# LMZ10500.net
KiCad netlist of a schematic drawn in Altium Designer
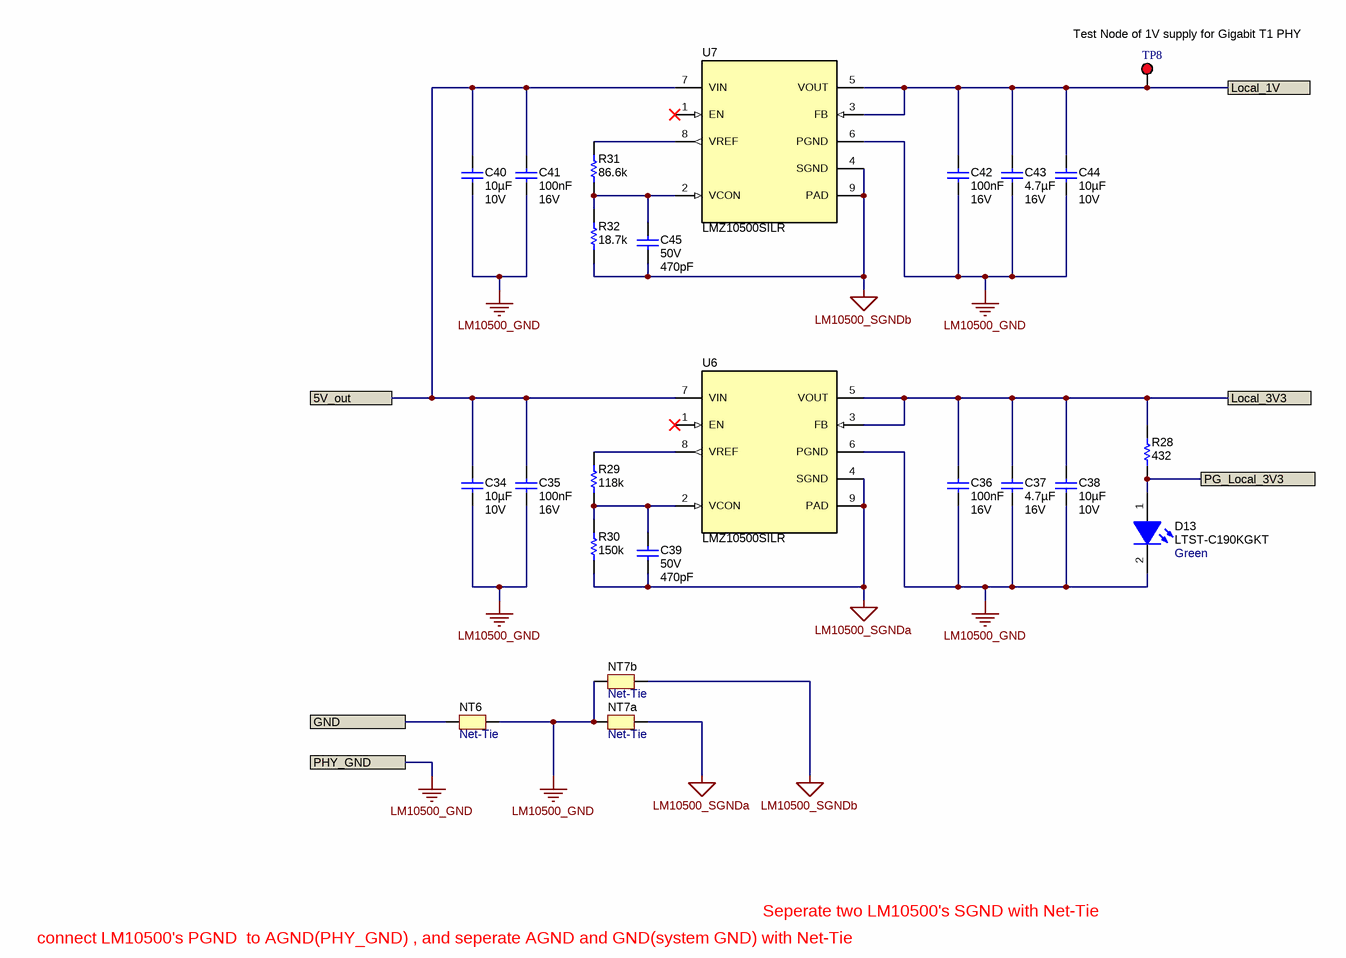
[diagram p0: LMZ10500.SchDoc]

(export (version "E")
  (design (tool "Eeschema 10.0.6"))
  (components
    (comp (ref "C34")
      (value "GRM188Z71A106MA73D")
      (footprint "0603")
      (description "CAP, CERM, 10 uF, 10 V, +/- 20%, X7R, 0603")
      (fields
        (field (name "MANUFACTURER") "MuRata")
        (field (name "CAP_F") "10µF")
        (field (name "VDC_V") "10V")
        (field (name "PUBLISHER") "Texas Instruments")
      )
      (libsource (lib "Altium Vault - TI") (part "Capacitor"))
    )
    (comp (ref "C35")
      (value "GRM188R71C104KA01D")
      (footprint "0603")
      (description "CAP, CERM, 0.1 uF, 16 V, +/- 10%, X7R, 0603")
      (fields
        (field (name "MANUFACTURER") "MuRata")
        (field (name "CAP_F") "100nF")
        (field (name "VDC_V") "16V")
        (field (name "PUBLISHER") "Texas Instruments")
      )
      (libsource (lib "Altium Vault - TI") (part "Capacitor"))
    )
    (comp (ref "C36")
      (value "GRM188R71C104KA01D")
      (footprint "0603")
      (description "CAP, CERM, 0.1 uF, 16 V, +/- 10%, X7R, 0603")
      (fields
        (field (name "MANUFACTURER") "MuRata")
        (field (name "CAP_F") "100nF")
        (field (name "VDC_V") "16V")
        (field (name "PUBLISHER") "Texas Instruments")
      )
      (libsource (lib "Altium Vault - TI") (part "Capacitor"))
    )
    (comp (ref "C37")
      (value "GRM188Z71C475KE21D")
      (footprint "0603")
      (description "CAP, CERM, 4.7 uF, 16 V,+/- 10%, X7R, 0603")
      (fields
        (field (name "MANUFACTURER") "MuRata")
        (field (name "CAP_F") "4.7µF")
        (field (name "VDC_V") "16V")
        (field (name "PUBLISHER") "Texas Instruments")
      )
      (libsource (lib "Altium Vault - TI") (part "Capacitor"))
    )
    (comp (ref "C38")
      (value "GRM188Z71A106MA73D")
      (footprint "0603")
      (description "CAP, CERM, 10 uF, 10 V, +/- 20%, X7R, 0603")
      (fields
        (field (name "MANUFACTURER") "MuRata")
        (field (name "CAP_F") "10µF")
        (field (name "VDC_V") "10V")
        (field (name "PUBLISHER") "Texas Instruments")
      )
      (libsource (lib "Altium Vault - TI") (part "Capacitor"))
    )
    (comp (ref "C39")
      (value "GCM155R71H471KA37D")
      (footprint "0402")
      (description "CAP, CERM, 470 pF, 50 V, +/- 10%, X7R, AEC-Q200 Grade 1, 0402")
      (fields
        (field (name "MANUFACTURER") "MuRata")
        (field (name "VDC_V") "50V")
        (field (name "VALUEDISPLAYED") "470pF")
        (field (name "PUBLISHER") "Texas Instruments")
      )
      (libsource (lib "Altium Vault - TI") (part "Capacitor"))
    )
    (comp (ref "C40")
      (value "GRM188Z71A106MA73D")
      (footprint "0603")
      (description "CAP, CERM, 10 uF, 10 V, +/- 20%, X7R, 0603")
      (fields
        (field (name "MANUFACTURER") "MuRata")
        (field (name "CAP_F") "10µF")
        (field (name "VDC_V") "10V")
        (field (name "PUBLISHER") "Texas Instruments")
      )
      (libsource (lib "Altium Vault - TI") (part "Capacitor"))
    )
    (comp (ref "C41")
      (value "GRM188R71C104KA01D")
      (footprint "0603")
      (description "CAP, CERM, 0.1 uF, 16 V, +/- 10%, X7R, 0603")
      (fields
        (field (name "MANUFACTURER") "MuRata")
        (field (name "CAP_F") "100nF")
        (field (name "VDC_V") "16V")
        (field (name "PUBLISHER") "Texas Instruments")
      )
      (libsource (lib "Altium Vault - TI") (part "Capacitor"))
    )
    (comp (ref "C42")
      (value "GRM188R71C104KA01D")
      (footprint "0603")
      (description "CAP, CERM, 0.1 uF, 16 V, +/- 10%, X7R, 0603")
      (fields
        (field (name "MANUFACTURER") "MuRata")
        (field (name "CAP_F") "100nF")
        (field (name "VDC_V") "16V")
        (field (name "PUBLISHER") "Texas Instruments")
      )
      (libsource (lib "Altium Vault - TI") (part "Capacitor"))
    )
    (comp (ref "C43")
      (value "GRM188Z71C475KE21D")
      (footprint "0603")
      (description "CAP, CERM, 4.7 uF, 16 V,+/- 10%, X7R, 0603")
      (fields
        (field (name "MANUFACTURER") "MuRata")
        (field (name "CAP_F") "4.7µF")
        (field (name "VDC_V") "16V")
        (field (name "PUBLISHER") "Texas Instruments")
      )
      (libsource (lib "Altium Vault - TI") (part "Capacitor"))
    )
    (comp (ref "C44")
      (value "GRM188Z71A106MA73D")
      (footprint "0603")
      (description "CAP, CERM, 10 uF, 10 V, +/- 20%, X7R, 0603")
      (fields
        (field (name "MANUFACTURER") "MuRata")
        (field (name "CAP_F") "10µF")
        (field (name "VDC_V") "10V")
        (field (name "PUBLISHER") "Texas Instruments")
      )
      (libsource (lib "Altium Vault - TI") (part "Capacitor"))
    )
    (comp (ref "C45")
      (value "GCM155R71H471KA37D")
      (footprint "0402")
      (description "CAP, CERM, 470 pF, 50 V, +/- 10%, X7R, AEC-Q200 Grade 1, 0402")
      (fields
        (field (name "MANUFACTURER") "MuRata")
        (field (name "VDC_V") "50V")
        (field (name "VALUEDISPLAYED") "470pF")
        (field (name "PUBLISHER") "Texas Instruments")
      )
      (libsource (lib "Altium Vault - TI") (part "Capacitor"))
    )
    (comp (ref "D13")
      (value "LTST-C190KGKT")
      (footprint "LED_LTST-C190_G")
      (description "LED, Green, SMD")
      (fields (field (name "ALTIUM_VALUE") "Green") (field (name "MANUFACTURER") "Lite-On"))
      (libsource (lib "Altium Vault - TI") (part "LED"))
    )
    (comp (ref "NT6")
      (value "Net-Tie")
      (footprint "Net-Tie_50milWide_30milLong")
      (description "Single point connection between nets.")
      (libsource (lib "Altium Vault - TI") (part "Net-Tie"))
    )
    (comp (ref "NT7a")
      (value "Net-Tie")
      (footprint "NetTie_0402")
      (description "Single point connection between nets.")
      (libsource (lib "Altium Vault - TI") (part "Net-Tie"))
    )
    (comp (ref "NT7b")
      (value "Net-Tie")
      (footprint "NetTie_0402")
      (description "Single point connection between nets.")
      (libsource (lib "Altium Vault - TI") (part "Net-Tie"))
    )
    (comp (ref "R28")
      (value "CRCW0603432RFKEA")
      (footprint "0603")
      (description "RES, 432, 1%, 0.1 W, AEC-Q200 Grade 0, 0603")
      (fields (field (name "MANUFACTURER") "Vishay-Dale") (field (name "VALUEDISPLAYED") "432"))
      (libsource (lib "Altium Vault - TI") (part "Resistor"))
    )
    (comp (ref "R29")
      (value "CRCW0402118KFKED")
      (footprint "0402")
      (description "RES, 118 k, 1%, 0.063 W, AEC-Q200 Grade 0, 0402")
      (fields (field (name "MANUFACTURER") "Vishay-Dale") (field (name "VALUEDISPLAYED") "118k"))
      (libsource (lib "Altium Vault - TI") (part "Resistor"))
    )
    (comp (ref "R30")
      (value "CRCW0402150KFKED")
      (footprint "0402")
      (description "RES, 150 k, 1%, 0.063 W, AEC-Q200 Grade 0, 0402")
      (fields (field (name "MANUFACTURER") "Vishay-Dale") (field (name "VALUEDISPLAYED") "150k"))
      (libsource (lib "Altium Vault - TI") (part "Resistor"))
    )
    (comp (ref "R31")
      (value "CRCW040286K6FKED")
      (footprint "0402")
      (description "RES, 86.6 k, 1%, 0.063 W, AEC-Q200 Grade 0, 0402")
      (fields (field (name "MANUFACTURER") "Vishay-Dale") (field (name "VALUEDISPLAYED") "86.6k"))
      (libsource (lib "Altium Vault - TI") (part "Resistor"))
    )
    (comp (ref "R32")
      (value "CRCW040218K7FKED")
      (footprint "0402")
      (description "RES, 18.7 k, 1%, 0.063 W, AEC-Q200 Grade 0, 0402")
      (fields (field (name "MANUFACTURER") "Vishay-Dale") (field (name "VALUEDISPLAYED") "18.7k"))
      (libsource (lib "Altium Vault - TI") (part "Resistor"))
    )
    (comp (ref "TP8")
      (value "5000")
      (footprint "Keystone5000")
      (description "Test Point, Miniature, Red, TH")
      (fields (field (name "MANUFACTURER") "Keystone") (field (name "PUBLISHER") "Texas Instruments"))
      (libsource (lib "Altium Vault - TI") (part "5000"))
    )
    (comp (ref "U6")
      (value "LMZ10500SILR")
      (footprint "SIL0008A")
      (description "2.7V to 5.5V, 650mA High Density Nano Module, SIL0008A (USIP-8)")
      (fields
        (field (name "PARTNUMBER") "LMZ10500SILR")
        (field (name "MANUFACTURER") "Texas Instruments")
        (field (name "ALTERNATE PARTNUMBER") "LMZ10500SILT")
      )
      (libsource (lib "Altium Vault - TI") (part "LMZ10501"))
    )
    (comp (ref "U7")
      (value "LMZ10500SILR")
      (footprint "SIL0008A")
      (description "2.7V to 5.5V, 650mA High Density Nano Module, SIL0008A (USIP-8)")
      (fields
        (field (name "PARTNUMBER") "LMZ10500SILR")
        (field (name "MANUFACTURER") "Texas Instruments")
        (field (name "ALTERNATE PARTNUMBER") "LMZ10500SILT")
      )
      (libsource (lib "Altium Vault - TI") (part "LMZ10501"))
    )
  )
  (nets
    (net (code "1") (name "/5V_out") (class "Default")
      (node (ref "C34") (pin "1") (pinfunction "1_1") (pintype "passive"))
      (node (ref "C35") (pin "1") (pinfunction "1_1") (pintype "passive"))
      (node (ref "C40") (pin "1") (pinfunction "1_1") (pintype "passive"))
      (node (ref "C41") (pin "1") (pinfunction "1_1") (pintype "passive"))
      (node (ref "U6") (pin "7") (pinfunction "VIN_7") (pintype "power_in"))
      (node (ref "U7") (pin "7") (pinfunction "VIN_7") (pintype "power_in"))
    )
    (net (code "2") (name "/GND") (class "Default")
      (node (ref "NT6") (pin "1") (pinfunction "1_1") (pintype "passive"))
    )
    (net (code "3") (name "/Local_1V") (class "Default")
      (node (ref "C42") (pin "1") (pinfunction "1_1") (pintype "passive"))
      (node (ref "C43") (pin "1") (pinfunction "1_1") (pintype "passive"))
      (node (ref "C44") (pin "1") (pinfunction "1_1") (pintype "passive"))
      (node (ref "TP8") (pin "1") (pintype "passive"))
      (node (ref "U7") (pin "3") (pinfunction "FB_3") (pintype "input"))
      (node (ref "U7") (pin "5") (pinfunction "VOUT_5") (pintype "power_in"))
    )
    (net (code "4") (name "/Local_3V3") (class "Default")
      (node (ref "C36") (pin "1") (pinfunction "1_1") (pintype "passive"))
      (node (ref "C37") (pin "1") (pinfunction "1_1") (pintype "passive"))
      (node (ref "C38") (pin "1") (pinfunction "1_1") (pintype "passive"))
      (node (ref "R28") (pin "2") (pinfunction "2_2") (pintype "passive"))
      (node (ref "U6") (pin "3") (pinfunction "FB_3") (pintype "input"))
      (node (ref "U6") (pin "5") (pinfunction "VOUT_5") (pintype "power_in"))
    )
    (net (code "5") (name "/PG_Local_3V3") (class "Default")
      (node (ref "D13") (pin "1") (pinfunction "A_1") (pintype "passive"))
      (node (ref "R28") (pin "1") (pinfunction "1_1") (pintype "passive"))
    )
    (net (code "6") (name "LM10500_GND") (class "Default")
      (node (ref "C34") (pin "2") (pinfunction "2_2") (pintype "passive"))
      (node (ref "C35") (pin "2") (pinfunction "2_2") (pintype "passive"))
      (node (ref "C36") (pin "2") (pinfunction "2_2") (pintype "passive"))
      (node (ref "C37") (pin "2") (pinfunction "2_2") (pintype "passive"))
      (node (ref "C38") (pin "2") (pinfunction "2_2") (pintype "passive"))
      (node (ref "C40") (pin "2") (pinfunction "2_2") (pintype "passive"))
      (node (ref "C41") (pin "2") (pinfunction "2_2") (pintype "passive"))
      (node (ref "C42") (pin "2") (pinfunction "2_2") (pintype "passive"))
      (node (ref "C43") (pin "2") (pinfunction "2_2") (pintype "passive"))
      (node (ref "C44") (pin "2") (pinfunction "2_2") (pintype "passive"))
      (node (ref "D13") (pin "2") (pinfunction "K_2") (pintype "passive"))
      (node (ref "NT6") (pin "2") (pinfunction "2_2") (pintype "passive"))
      (node (ref "NT7a") (pin "1") (pinfunction "1_1") (pintype "passive"))
      (node (ref "NT7b") (pin "1") (pinfunction "1_1") (pintype "passive"))
      (node (ref "U6") (pin "6") (pinfunction "PGND_6") (pintype "power_in"))
      (node (ref "U7") (pin "6") (pinfunction "PGND_6") (pintype "power_in"))
    )
    (net (code "7") (name "LM10500_SGNDa") (class "Default")
      (node (ref "C39") (pin "2") (pinfunction "2_2") (pintype "passive"))
      (node (ref "NT7a") (pin "2") (pinfunction "2_2") (pintype "passive"))
      (node (ref "R30") (pin "1") (pinfunction "1_1") (pintype "passive"))
      (node (ref "U6") (pin "4") (pinfunction "SGND_4") (pintype "power_in"))
      (node (ref "U6") (pin "9") (pinfunction "PAD_9") (pintype "power_in"))
    )
    (net (code "8") (name "LM10500_SGNDb") (class "Default")
      (node (ref "C45") (pin "2") (pinfunction "2_2") (pintype "passive"))
      (node (ref "NT7b") (pin "2") (pinfunction "2_2") (pintype "passive"))
      (node (ref "R32") (pin "1") (pinfunction "1_1") (pintype "passive"))
      (node (ref "U7") (pin "4") (pinfunction "SGND_4") (pintype "power_in"))
      (node (ref "U7") (pin "9") (pinfunction "PAD_9") (pintype "power_in"))
    )
    (net (code "9") (name "Net-(U6-VCON)") (class "Default")
      (node (ref "C39") (pin "1") (pinfunction "1_1") (pintype "passive"))
      (node (ref "R29") (pin "1") (pinfunction "1_1") (pintype "passive"))
      (node (ref "R30") (pin "2") (pinfunction "2_2") (pintype "passive"))
      (node (ref "U6") (pin "2") (pinfunction "VCON_2") (pintype "input"))
    )
    (net (code "10") (name "Net-(U6-VREF)") (class "Default")
      (node (ref "R29") (pin "2") (pinfunction "2_2") (pintype "passive"))
      (node (ref "U6") (pin "8") (pinfunction "VREF_8") (pintype "output"))
    )
    (net (code "11") (name "Net-(U7-VCON)") (class "Default")
      (node (ref "C45") (pin "1") (pinfunction "1_1") (pintype "passive"))
      (node (ref "R31") (pin "1") (pinfunction "1_1") (pintype "passive"))
      (node (ref "R32") (pin "2") (pinfunction "2_2") (pintype "passive"))
      (node (ref "U7") (pin "2") (pinfunction "VCON_2") (pintype "input"))
    )
    (net (code "12") (name "Net-(U7-VREF)") (class "Default")
      (node (ref "R31") (pin "2") (pinfunction "2_2") (pintype "passive"))
      (node (ref "U7") (pin "8") (pinfunction "VREF_8") (pintype "output"))
    )
    (net (code "13") (name "unconnected-(U6-EN-Pad1)") (class "Default")
      (node (ref "U6") (pin "1") (pinfunction "EN_1") (pintype "input+no_connect"))
    )
    (net (code "14") (name "unconnected-(U7-EN-Pad1)") (class "Default")
      (node (ref "U7") (pin "1") (pinfunction "EN_1") (pintype "input+no_connect"))
    )
  )
)
